# board2sided.net
KiCad netlist of a schematic drawn in EAGLE
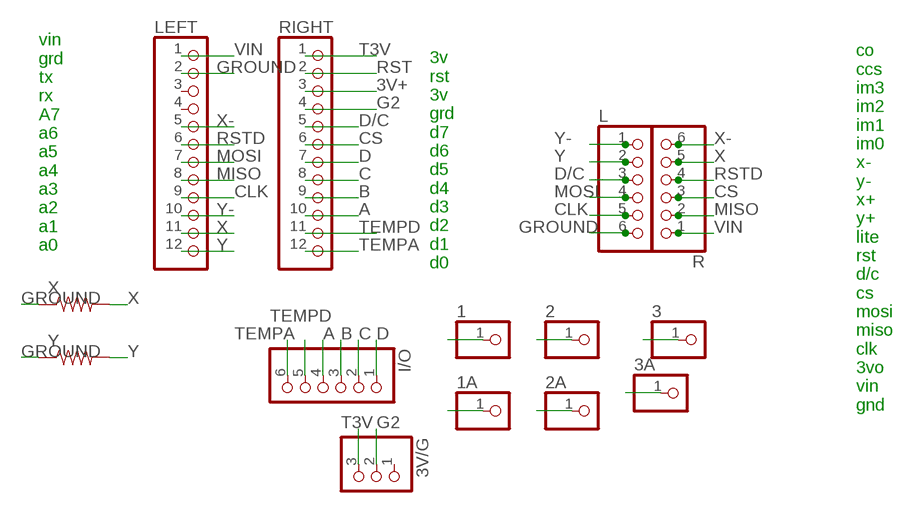
[diagram p0: schematic, sheet 1]

(export (version "E")
  (design (tool "Eeschema 10.0.6"))
  (components
    (comp (ref "1")
      (value "PINHD-1X1CB")
      (footprint "eagle-import:1X01-CLEANBIG")
      (libsource (lib "eagle-import") (part "PINHD-1X1CB"))
    )
    (comp (ref "1A")
      (value "PINHD-1X1CB")
      (footprint "eagle-import:1X01-CLEANBIG")
      (libsource (lib "eagle-import") (part "PINHD-1X1CB"))
    )
    (comp (ref "2")
      (value "PINHD-1X1CB")
      (footprint "eagle-import:1X01-CLEANBIG")
      (libsource (lib "eagle-import") (part "PINHD-1X1CB"))
    )
    (comp (ref "2A")
      (value "PINHD-1X1CB")
      (footprint "eagle-import:1X01-CLEANBIG")
      (libsource (lib "eagle-import") (part "PINHD-1X1CB"))
    )
    (comp (ref "3")
      (value "PINHD-1X1CB")
      (footprint "eagle-import:1X01-CLEANBIG")
      (libsource (lib "eagle-import") (part "PINHD-1X1CB"))
    )
    (comp (ref "3A")
      (value "PINHD-1X1CB")
      (footprint "eagle-import:1X01-CLEANBIG")
      (libsource (lib "eagle-import") (part "PINHD-1X1CB"))
    )
    (comp (ref "3V/G")
      (value "PINHD-1X3CB")
      (footprint "eagle-import:1X03-CLEANBIG")
      (libsource (lib "eagle-import") (part "PINHD-1X3CB"))
    )
    (comp (ref "I/O")
      (value "PINHD-1X6CB")
      (footprint "eagle-import:1X06-CLEANBIG")
      (libsource (lib "eagle-import") (part "PINHD-1X6CB"))
    )
    (comp (ref "L")
      (value "PINHD-1X6CB")
      (footprint "eagle-import:1X06-CLEANBIG")
      (libsource (lib "eagle-import") (part "PINHD-1X6CB"))
    )
    (comp (ref "LEFT")
      (value "PINHD-1X12-CB")
      (footprint "eagle-import:1X12-CB")
      (libsource (lib "eagle-import") (part "PINHD-1X12-CB"))
    )
    (comp (ref "R")
      (value "PINHD-1X6CB")
      (footprint "eagle-import:1X06-CLEANBIG")
      (libsource (lib "eagle-import") (part "PINHD-1X6CB"))
    )
    (comp (ref "RIGHT")
      (value "PINHD-1X12-CB")
      (footprint "eagle-import:1X12-CB")
      (libsource (lib "eagle-import") (part "PINHD-1X12-CB"))
    )
    (comp (ref "X")
      (value "10KOHM-1/6W-5%(PTH)KIT")
      (footprint "eagle-import:AXIAL-0.3-KIT")
      (libsource (lib "eagle-import") (part "10KOHM-1/6W-5%(PTH)KIT"))
    )
    (comp (ref "Y")
      (value "10KOHM-1/6W-5%(PTH)KIT")
      (footprint "eagle-import:AXIAL-0.3-KIT")
      (libsource (lib "eagle-import") (part "10KOHM-1/6W-5%(PTH)KIT"))
    )
  )
  (nets
    (net (code "1") (name "/1") (class "Default")
      (node (ref "1") (pin "1") (pinfunction "1_1") (pintype "passive"))
      (node (ref "1A") (pin "1") (pinfunction "1_1") (pintype "passive"))
    )
    (net (code "2") (name "/2") (class "Default")
      (node (ref "2") (pin "1") (pinfunction "1_1") (pintype "passive"))
      (node (ref "2A") (pin "1") (pinfunction "1_1") (pintype "passive"))
    )
    (net (code "3") (name "/3") (class "Default")
      (node (ref "3") (pin "1") (pinfunction "1_1") (pintype "passive"))
      (node (ref "3A") (pin "1") (pinfunction "1_1") (pintype "passive"))
    )
    (net (code "4") (name "/3V+") (class "Default")
      (node (ref "RIGHT") (pin "3") (pinfunction "3_3") (pintype "passive"))
    )
    (net (code "5") (name "/A") (class "Default")
      (node (ref "I/O") (pin "4") (pinfunction "4_4") (pintype "passive"))
      (node (ref "RIGHT") (pin "10") (pinfunction "10_10") (pintype "passive"))
    )
    (net (code "6") (name "/B") (class "Default")
      (node (ref "I/O") (pin "3") (pinfunction "3_3") (pintype "passive"))
      (node (ref "RIGHT") (pin "9") (pinfunction "9_9") (pintype "passive"))
    )
    (net (code "7") (name "/C") (class "Default")
      (node (ref "I/O") (pin "2") (pinfunction "2_2") (pintype "passive"))
      (node (ref "RIGHT") (pin "8") (pinfunction "8_8") (pintype "passive"))
    )
    (net (code "8") (name "/CLK") (class "Default")
      (node (ref "L") (pin "5") (pinfunction "5_5") (pintype "passive"))
      (node (ref "LEFT") (pin "9") (pinfunction "9_9") (pintype "passive"))
    )
    (net (code "9") (name "/CS") (class "Default")
      (node (ref "R") (pin "3") (pinfunction "3_3") (pintype "passive"))
      (node (ref "RIGHT") (pin "6") (pinfunction "6_6") (pintype "passive"))
    )
    (net (code "10") (name "/D") (class "Default")
      (node (ref "I/O") (pin "1") (pinfunction "1_1") (pintype "passive"))
      (node (ref "RIGHT") (pin "7") (pinfunction "7_7") (pintype "passive"))
    )
    (net (code "11") (name "/D{slash}C") (class "Default")
      (node (ref "L") (pin "3") (pinfunction "3_3") (pintype "passive"))
      (node (ref "RIGHT") (pin "5") (pinfunction "5_5") (pintype "passive"))
    )
    (net (code "12") (name "/G2") (class "Default")
      (node (ref "3V/G") (pin "2") (pinfunction "2_2") (pintype "passive"))
      (node (ref "RIGHT") (pin "4") (pinfunction "4_4") (pintype "passive"))
    )
    (net (code "13") (name "/GROUND") (class "Default")
      (node (ref "L") (pin "6") (pinfunction "6_6") (pintype "passive"))
      (node (ref "LEFT") (pin "2") (pinfunction "2_2") (pintype "passive"))
      (node (ref "X") (pin "P$1") (pinfunction "1_P$1") (pintype "passive"))
      (node (ref "Y") (pin "P$1") (pinfunction "1_P$1") (pintype "passive"))
    )
    (net (code "14") (name "/MISO") (class "Default")
      (node (ref "LEFT") (pin "8") (pinfunction "8_8") (pintype "passive"))
      (node (ref "R") (pin "2") (pinfunction "2_2") (pintype "passive"))
    )
    (net (code "15") (name "/MOSI") (class "Default")
      (node (ref "L") (pin "4") (pinfunction "4_4") (pintype "passive"))
      (node (ref "LEFT") (pin "7") (pinfunction "7_7") (pintype "passive"))
    )
    (net (code "16") (name "/RST") (class "Default")
      (node (ref "RIGHT") (pin "2") (pinfunction "2_2") (pintype "passive"))
    )
    (net (code "17") (name "/RSTD") (class "Default")
      (node (ref "LEFT") (pin "6") (pinfunction "6_6") (pintype "passive"))
      (node (ref "R") (pin "4") (pinfunction "4_4") (pintype "passive"))
    )
    (net (code "18") (name "/T3V") (class "Default")
      (node (ref "3V/G") (pin "3") (pinfunction "3_3") (pintype "passive"))
      (node (ref "RIGHT") (pin "1") (pinfunction "1_1") (pintype "passive"))
    )
    (net (code "19") (name "/TEMPA") (class "Default")
      (node (ref "I/O") (pin "6") (pinfunction "6_6") (pintype "passive"))
      (node (ref "RIGHT") (pin "12") (pinfunction "12_12") (pintype "passive"))
    )
    (net (code "20") (name "/TEMPD") (class "Default")
      (node (ref "I/O") (pin "5") (pinfunction "5_5") (pintype "passive"))
      (node (ref "RIGHT") (pin "11") (pinfunction "11_11") (pintype "passive"))
    )
    (net (code "21") (name "/VIN") (class "Default")
      (node (ref "LEFT") (pin "1") (pinfunction "1_1") (pintype "passive"))
      (node (ref "R") (pin "1") (pinfunction "1_1") (pintype "passive"))
    )
    (net (code "22") (name "/X") (class "Default")
      (node (ref "LEFT") (pin "11") (pinfunction "11_11") (pintype "passive"))
      (node (ref "R") (pin "5") (pinfunction "5_5") (pintype "passive"))
      (node (ref "X") (pin "P$2") (pinfunction "2_P$2") (pintype "passive"))
    )
    (net (code "23") (name "/X-") (class "Default")
      (node (ref "LEFT") (pin "5") (pinfunction "5_5") (pintype "passive"))
      (node (ref "R") (pin "6") (pinfunction "6_6") (pintype "passive"))
    )
    (net (code "24") (name "/Y") (class "Default")
      (node (ref "L") (pin "2") (pinfunction "2_2") (pintype "passive"))
      (node (ref "LEFT") (pin "12") (pinfunction "12_12") (pintype "passive"))
      (node (ref "Y") (pin "P$2") (pinfunction "2_P$2") (pintype "passive"))
    )
    (net (code "25") (name "/Y-") (class "Default")
      (node (ref "L") (pin "1") (pinfunction "1_1") (pintype "passive"))
      (node (ref "LEFT") (pin "10") (pinfunction "10_10") (pintype "passive"))
    )
    (net (code "26") (name "unconnected-(3V/G-Pad1)") (class "Default")
      (node (ref "3V/G") (pin "1") (pinfunction "1_1") (pintype "passive"))
    )
    (net (code "27") (name "unconnected-(LEFT-Pad3)") (class "Default")
      (node (ref "LEFT") (pin "3") (pinfunction "3_3") (pintype "passive"))
    )
    (net (code "28") (name "unconnected-(LEFT-Pad4)") (class "Default")
      (node (ref "LEFT") (pin "4") (pinfunction "4_4") (pintype "passive"))
    )
  )
)
